# Sensor_QRD1114.net
KiCad netlist of a schematic drawn in EAGLE
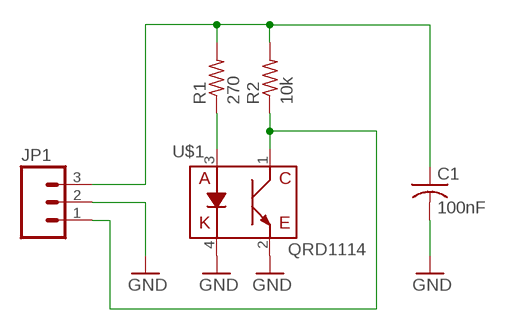
[diagram p0: schematic, sheet 1]

(export (version "E")
  (design (tool "Eeschema 10.0.6"))
  (components
    (comp (ref "C1")
      (value "100nF")
      (footprint "eagle-import:C025-024X044")
      (libsource (lib "eagle-import") (part "C-US025-024X044"))
    )
    (comp (ref "JP1")
      (value "M03LOCK_LONGPADS")
      (footprint "eagle-import:1X03_LOCK_LONGPADS")
      (libsource (lib "eagle-import") (part "M03LOCK_LONGPADS"))
    )
    (comp (ref "R1")
      (value "270")
      (footprint "eagle-import:0207_7")
      (libsource (lib "eagle-import") (part "R-US_0207/7"))
    )
    (comp (ref "R2")
      (value "10k")
      (footprint "eagle-import:0207_7")
      (libsource (lib "eagle-import") (part "R-US_0207/7"))
    )
    (comp (ref "U$1")
      (value "QRD1114")
      (footprint "eagle-import:QRD1114")
      (libsource (lib "eagle-import") (part "QRD1114"))
    )
  )
  (nets
    (net (code "1") (name "GND") (class "Default")
      (node (ref "C1") (pin "2") (pinfunction "2_2") (pintype "passive"))
      (node (ref "JP1") (pin "2") (pinfunction "2_2") (pintype "passive"))
      (node (ref "U$1") (pin "2") (pinfunction "C_2") (pintype "bidirectional"))
      (node (ref "U$1") (pin "4") (pinfunction "K_4") (pintype "bidirectional"))
    )
    (net (code "2") (name "Net-(C1-Pad1)") (class "Default")
      (node (ref "C1") (pin "1") (pinfunction "1_1") (pintype "passive"))
      (node (ref "JP1") (pin "3") (pinfunction "3_3") (pintype "passive"))
      (node (ref "R1") (pin "2") (pinfunction "2_2") (pintype "passive"))
      (node (ref "R2") (pin "2") (pinfunction "2_2") (pintype "passive"))
    )
    (net (code "3") (name "Net-(U$1-A)") (class "Default")
      (node (ref "R1") (pin "1") (pinfunction "1_1") (pintype "passive"))
      (node (ref "U$1") (pin "3") (pinfunction "A_3") (pintype "bidirectional"))
    )
    (net (code "4") (name "Net-(U$1-E)") (class "Default")
      (node (ref "JP1") (pin "1") (pinfunction "1_1") (pintype "passive"))
      (node (ref "R2") (pin "1") (pinfunction "1_1") (pintype "passive"))
      (node (ref "U$1") (pin "1") (pinfunction "E_1") (pintype "bidirectional"))
    )
  )
)
